# Datalogging_SMD_Prototye.net
KiCad netlist of a schematic drawn in EAGLE
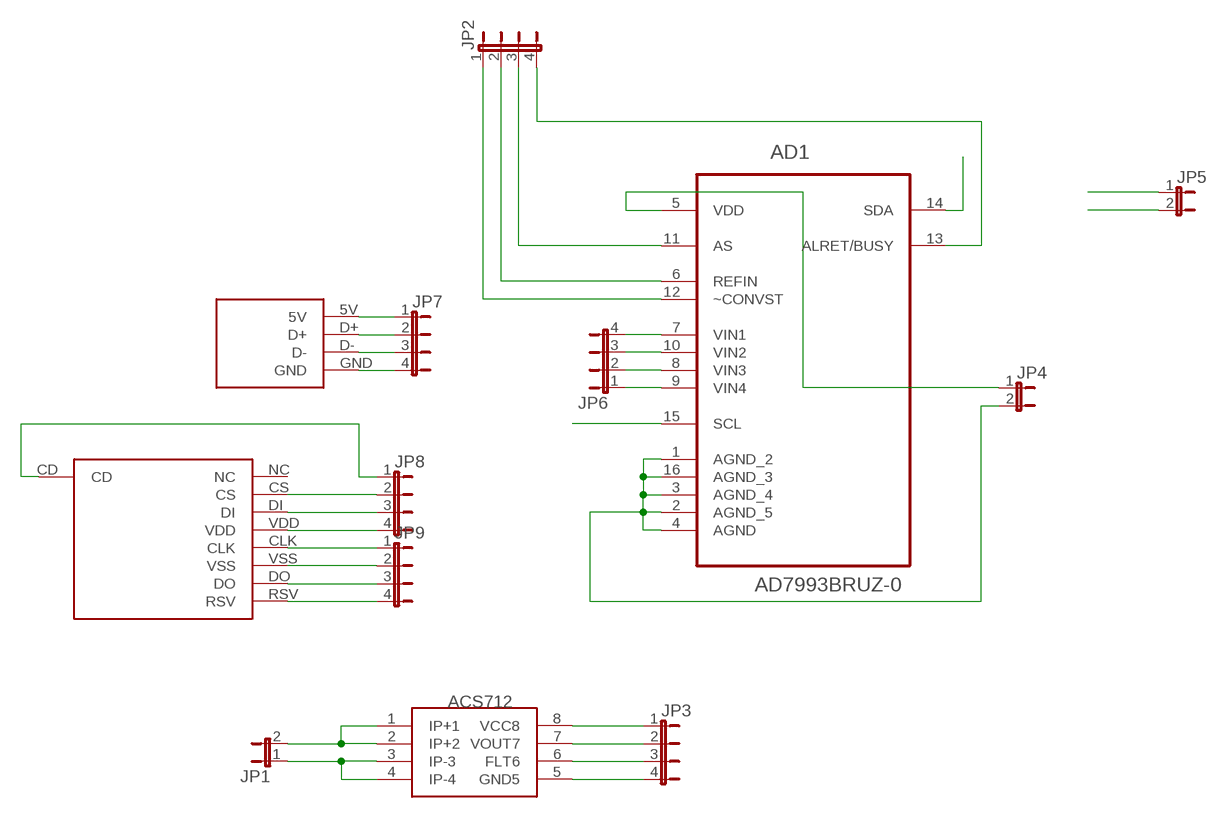
[diagram p0: schematic, sheet 1]

(export (version "E")
  (design (tool "Eeschema 10.0.6"))
  (components
    (comp (ref "AD1")
      (value "AD7993BRUZ-0")
      (footprint "eagle-import:SOP65P640X120-16N")
      (fields
        (field (name "MPN") "AD7993BRUZ-0")
        (field (name "OC_FARNELL") "1078309")
        (field (name "OC_NEWARK") "59K6101")
        (field (name "PACKAGE") "TSSOP-16")
        (field (name "SUPPLIER") "Analog Devices")
      )
      (libsource (lib "eagle-import") (part "AD7993BRUZ-0"))
    )
    (comp (ref "JP1")
      (value "JP1E")
      (footprint "eagle-import:JP1")
      (libsource (lib "eagle-import") (part "JP1E"))
    )
    (comp (ref "JP2")
      (value "JP4E")
      (footprint "eagle-import:JP4")
      (libsource (lib "eagle-import") (part "JP4E"))
    )
    (comp (ref "JP3")
      (value "JP4E")
      (footprint "eagle-import:JP4")
      (libsource (lib "eagle-import") (part "JP4E"))
    )
    (comp (ref "JP4")
      (value "JP1E")
      (footprint "eagle-import:JP1")
      (libsource (lib "eagle-import") (part "JP1E"))
    )
    (comp (ref "JP5")
      (value "JP1E")
      (footprint "eagle-import:JP1")
      (libsource (lib "eagle-import") (part "JP1E"))
    )
    (comp (ref "JP6")
      (value "JP4E")
      (footprint "eagle-import:JP4")
      (libsource (lib "eagle-import") (part "JP4E"))
    )
    (comp (ref "JP7")
      (value "JP4E")
      (footprint "eagle-import:JP4")
      (libsource (lib "eagle-import") (part "JP4E"))
    )
    (comp (ref "JP8")
      (value "JP4E")
      (footprint "eagle-import:JP4")
      (libsource (lib "eagle-import") (part "JP4E"))
    )
    (comp (ref "JP9")
      (value "JP4E")
      (footprint "eagle-import:JP4")
      (libsource (lib "eagle-import") (part "JP4E"))
    )
    (comp (ref "U$1")
      (value "USBA_SOCKET")
      (footprint "eagle-import:USBA_SOCKET")
      (libsource (lib "eagle-import") (part "USBA_SOCKET"))
    )
    (comp (ref "U$2")
      (value "ACS712")
      (footprint "eagle-import:SO8")
      (libsource (lib "eagle-import") (part "ACS712"))
    )
    (comp (ref "U$3")
      (value "MICROSD_SOCKET")
      (footprint "eagle-import:MICROSD_SOCKET")
      (libsource (lib "eagle-import") (part "MICROSD_SOCKET"))
    )
  )
  (nets
    (net (code "1") (name "/SCL") (class "Default")
      (node (ref "AD1") (pin "15") (pinfunction "SCL_15") (pintype "input"))
      (node (ref "JP5") (pin "2") (pinfunction "2_2") (pintype "passive"))
    )
    (net (code "2") (name "/SDA") (class "Default")
      (node (ref "AD1") (pin "14") (pinfunction "SDA_14") (pintype "bidirectional"))
      (node (ref "JP5") (pin "1") (pinfunction "1_1") (pintype "passive"))
    )
    (net (code "3") (name "Net-(AD1-AGND)") (class "Default")
      (node (ref "AD1") (pin "1") (pinfunction "AGND_2_1") (pintype "passive"))
      (node (ref "AD1") (pin "16") (pinfunction "AGND_3_16") (pintype "passive"))
      (node (ref "AD1") (pin "2") (pinfunction "AGND_5_2") (pintype "passive"))
      (node (ref "AD1") (pin "3") (pinfunction "AGND_4_3") (pintype "passive"))
      (node (ref "AD1") (pin "4") (pinfunction "AGND_4") (pintype "passive"))
      (node (ref "JP4") (pin "2") (pinfunction "2_2") (pintype "passive"))
    )
    (net (code "4") (name "Net-(AD1-ALRET{slash}BUSY)") (class "Default")
      (node (ref "AD1") (pin "13") (pinfunction "ALRET/BUSY_13") (pintype "output"))
      (node (ref "JP2") (pin "4") (pinfunction "4_4") (pintype "passive"))
    )
    (net (code "5") (name "Net-(AD1-AS)") (class "Default")
      (node (ref "AD1") (pin "11") (pinfunction "AS_11") (pintype "input"))
      (node (ref "JP2") (pin "3") (pinfunction "3_3") (pintype "passive"))
    )
    (net (code "6") (name "Net-(AD1-REFIN)") (class "Default")
      (node (ref "AD1") (pin "6") (pinfunction "REFIN_6") (pintype "input"))
      (node (ref "JP2") (pin "2") (pinfunction "2_2") (pintype "passive"))
    )
    (net (code "7") (name "Net-(AD1-VDD)") (class "Default")
      (node (ref "AD1") (pin "5") (pinfunction "VDD_5") (pintype "power_in"))
      (node (ref "JP4") (pin "1") (pinfunction "1_1") (pintype "passive"))
    )
    (net (code "8") (name "Net-(AD1-VIN1)") (class "Default")
      (node (ref "AD1") (pin "7") (pinfunction "VIN1_7") (pintype "input"))
      (node (ref "JP6") (pin "4") (pinfunction "4_4") (pintype "passive"))
    )
    (net (code "9") (name "Net-(AD1-VIN2)") (class "Default")
      (node (ref "AD1") (pin "10") (pinfunction "VIN2_10") (pintype "input"))
      (node (ref "JP6") (pin "3") (pinfunction "3_3") (pintype "passive"))
    )
    (net (code "10") (name "Net-(AD1-VIN3)") (class "Default")
      (node (ref "AD1") (pin "8") (pinfunction "VIN3_8") (pintype "input"))
      (node (ref "JP6") (pin "2") (pinfunction "2_2") (pintype "passive"))
    )
    (net (code "11") (name "Net-(AD1-VIN4)") (class "Default")
      (node (ref "AD1") (pin "9") (pinfunction "VIN4_9") (pintype "input"))
      (node (ref "JP6") (pin "1") (pinfunction "1_1") (pintype "passive"))
    )
    (net (code "12") (name "Net-(AD1-~{CONVST})") (class "Default")
      (node (ref "AD1") (pin "12") (pinfunction "~{CONVST}_12") (pintype "input"))
      (node (ref "JP2") (pin "1") (pinfunction "1_1") (pintype "passive"))
    )
    (net (code "13") (name "Net-(JP7-Pad1)") (class "Default")
      (node (ref "JP7") (pin "1") (pinfunction "1_1") (pintype "passive"))
      (node (ref "U$1") (pin "5V") (pinfunction "5V_5V") (pintype "bidirectional"))
    )
    (net (code "14") (name "Net-(JP7-Pad2)") (class "Default")
      (node (ref "JP7") (pin "2") (pinfunction "2_2") (pintype "passive"))
      (node (ref "U$1") (pin "D+") (pinfunction "D+_D+") (pintype "bidirectional"))
    )
    (net (code "15") (name "Net-(JP7-Pad3)") (class "Default")
      (node (ref "JP7") (pin "3") (pinfunction "3_3") (pintype "passive"))
      (node (ref "U$1") (pin "D-") (pinfunction "D-_D-") (pintype "bidirectional"))
    )
    (net (code "16") (name "Net-(JP7-Pad4)") (class "Default")
      (node (ref "JP7") (pin "4") (pinfunction "4_4") (pintype "passive"))
      (node (ref "U$1") (pin "GND") (pinfunction "GND_GND") (pintype "bidirectional"))
    )
    (net (code "17") (name "Net-(JP8-Pad1)") (class "Default")
      (node (ref "JP8") (pin "1") (pinfunction "1_1") (pintype "passive"))
      (node (ref "U$3") (pin "CD") (pinfunction "CD_CD") (pintype "bidirectional"))
    )
    (net (code "18") (name "Net-(JP8-Pad2)") (class "Default")
      (node (ref "JP8") (pin "2") (pinfunction "2_2") (pintype "passive"))
      (node (ref "U$3") (pin "CS") (pinfunction "CS_CS") (pintype "bidirectional"))
    )
    (net (code "19") (name "Net-(JP8-Pad3)") (class "Default")
      (node (ref "JP8") (pin "3") (pinfunction "3_3") (pintype "passive"))
      (node (ref "U$3") (pin "DI") (pinfunction "DI_DI") (pintype "bidirectional"))
    )
    (net (code "20") (name "Net-(JP8-Pad4)") (class "Default")
      (node (ref "JP8") (pin "4") (pinfunction "4_4") (pintype "passive"))
      (node (ref "U$3") (pin "VDD") (pinfunction "VDD_VDD") (pintype "bidirectional"))
    )
    (net (code "21") (name "Net-(JP9-Pad1)") (class "Default")
      (node (ref "JP9") (pin "1") (pinfunction "1_1") (pintype "passive"))
      (node (ref "U$3") (pin "CLK") (pinfunction "CLK_CLK") (pintype "bidirectional"))
    )
    (net (code "22") (name "Net-(JP9-Pad2)") (class "Default")
      (node (ref "JP9") (pin "2") (pinfunction "2_2") (pintype "passive"))
      (node (ref "U$3") (pin "VSS") (pinfunction "VSS_VSS") (pintype "bidirectional"))
    )
    (net (code "23") (name "Net-(JP9-Pad3)") (class "Default")
      (node (ref "JP9") (pin "3") (pinfunction "3_3") (pintype "passive"))
      (node (ref "U$3") (pin "DO") (pinfunction "DO_DO") (pintype "bidirectional"))
    )
    (net (code "24") (name "Net-(JP9-Pad4)") (class "Default")
      (node (ref "JP9") (pin "4") (pinfunction "4_4") (pintype "passive"))
      (node (ref "U$3") (pin "RSV") (pinfunction "RSV_RSV") (pintype "bidirectional"))
    )
    (net (code "25") (name "Net-(U$2-FLT6)") (class "Default")
      (node (ref "JP3") (pin "3") (pinfunction "3_3") (pintype "passive"))
      (node (ref "U$2") (pin "6") (pinfunction "FLT6_6") (pintype "passive"))
    )
    (net (code "26") (name "Net-(U$2-GND5)") (class "Default")
      (node (ref "JP3") (pin "4") (pinfunction "4_4") (pintype "passive"))
      (node (ref "U$2") (pin "5") (pinfunction "GND5_5") (pintype "power_in"))
    )
    (net (code "27") (name "Net-(U$2-IP+1)") (class "Default")
      (node (ref "JP1") (pin "2") (pinfunction "2_2") (pintype "passive"))
      (node (ref "U$2") (pin "1") (pinfunction "IP+1_1") (pintype "bidirectional"))
      (node (ref "U$2") (pin "2") (pinfunction "IP+2_2") (pintype "bidirectional"))
    )
    (net (code "28") (name "Net-(U$2-IP-3)") (class "Default")
      (node (ref "JP1") (pin "1") (pinfunction "1_1") (pintype "passive"))
      (node (ref "U$2") (pin "3") (pinfunction "IP-3_3") (pintype "bidirectional"))
      (node (ref "U$2") (pin "4") (pinfunction "IP-4_4") (pintype "bidirectional"))
    )
    (net (code "29") (name "Net-(U$2-VCC8)") (class "Default")
      (node (ref "JP3") (pin "1") (pinfunction "1_1") (pintype "passive"))
      (node (ref "U$2") (pin "8") (pinfunction "VCC8_8") (pintype "power_in"))
    )
    (net (code "30") (name "Net-(U$2-VOUT7)") (class "Default")
      (node (ref "JP3") (pin "2") (pinfunction "2_2") (pintype "passive"))
      (node (ref "U$2") (pin "7") (pinfunction "VOUT7_7") (pintype "output"))
    )
    (net (code "31") (name "unconnected-(U$3-PadNC)") (class "Default")
      (node (ref "U$3") (pin "NC") (pinfunction "NC_NC") (pintype "bidirectional"))
    )
  )
)
